# Lacrosse_Ball.net
KiCad netlist of a schematic drawn in Altium Designer
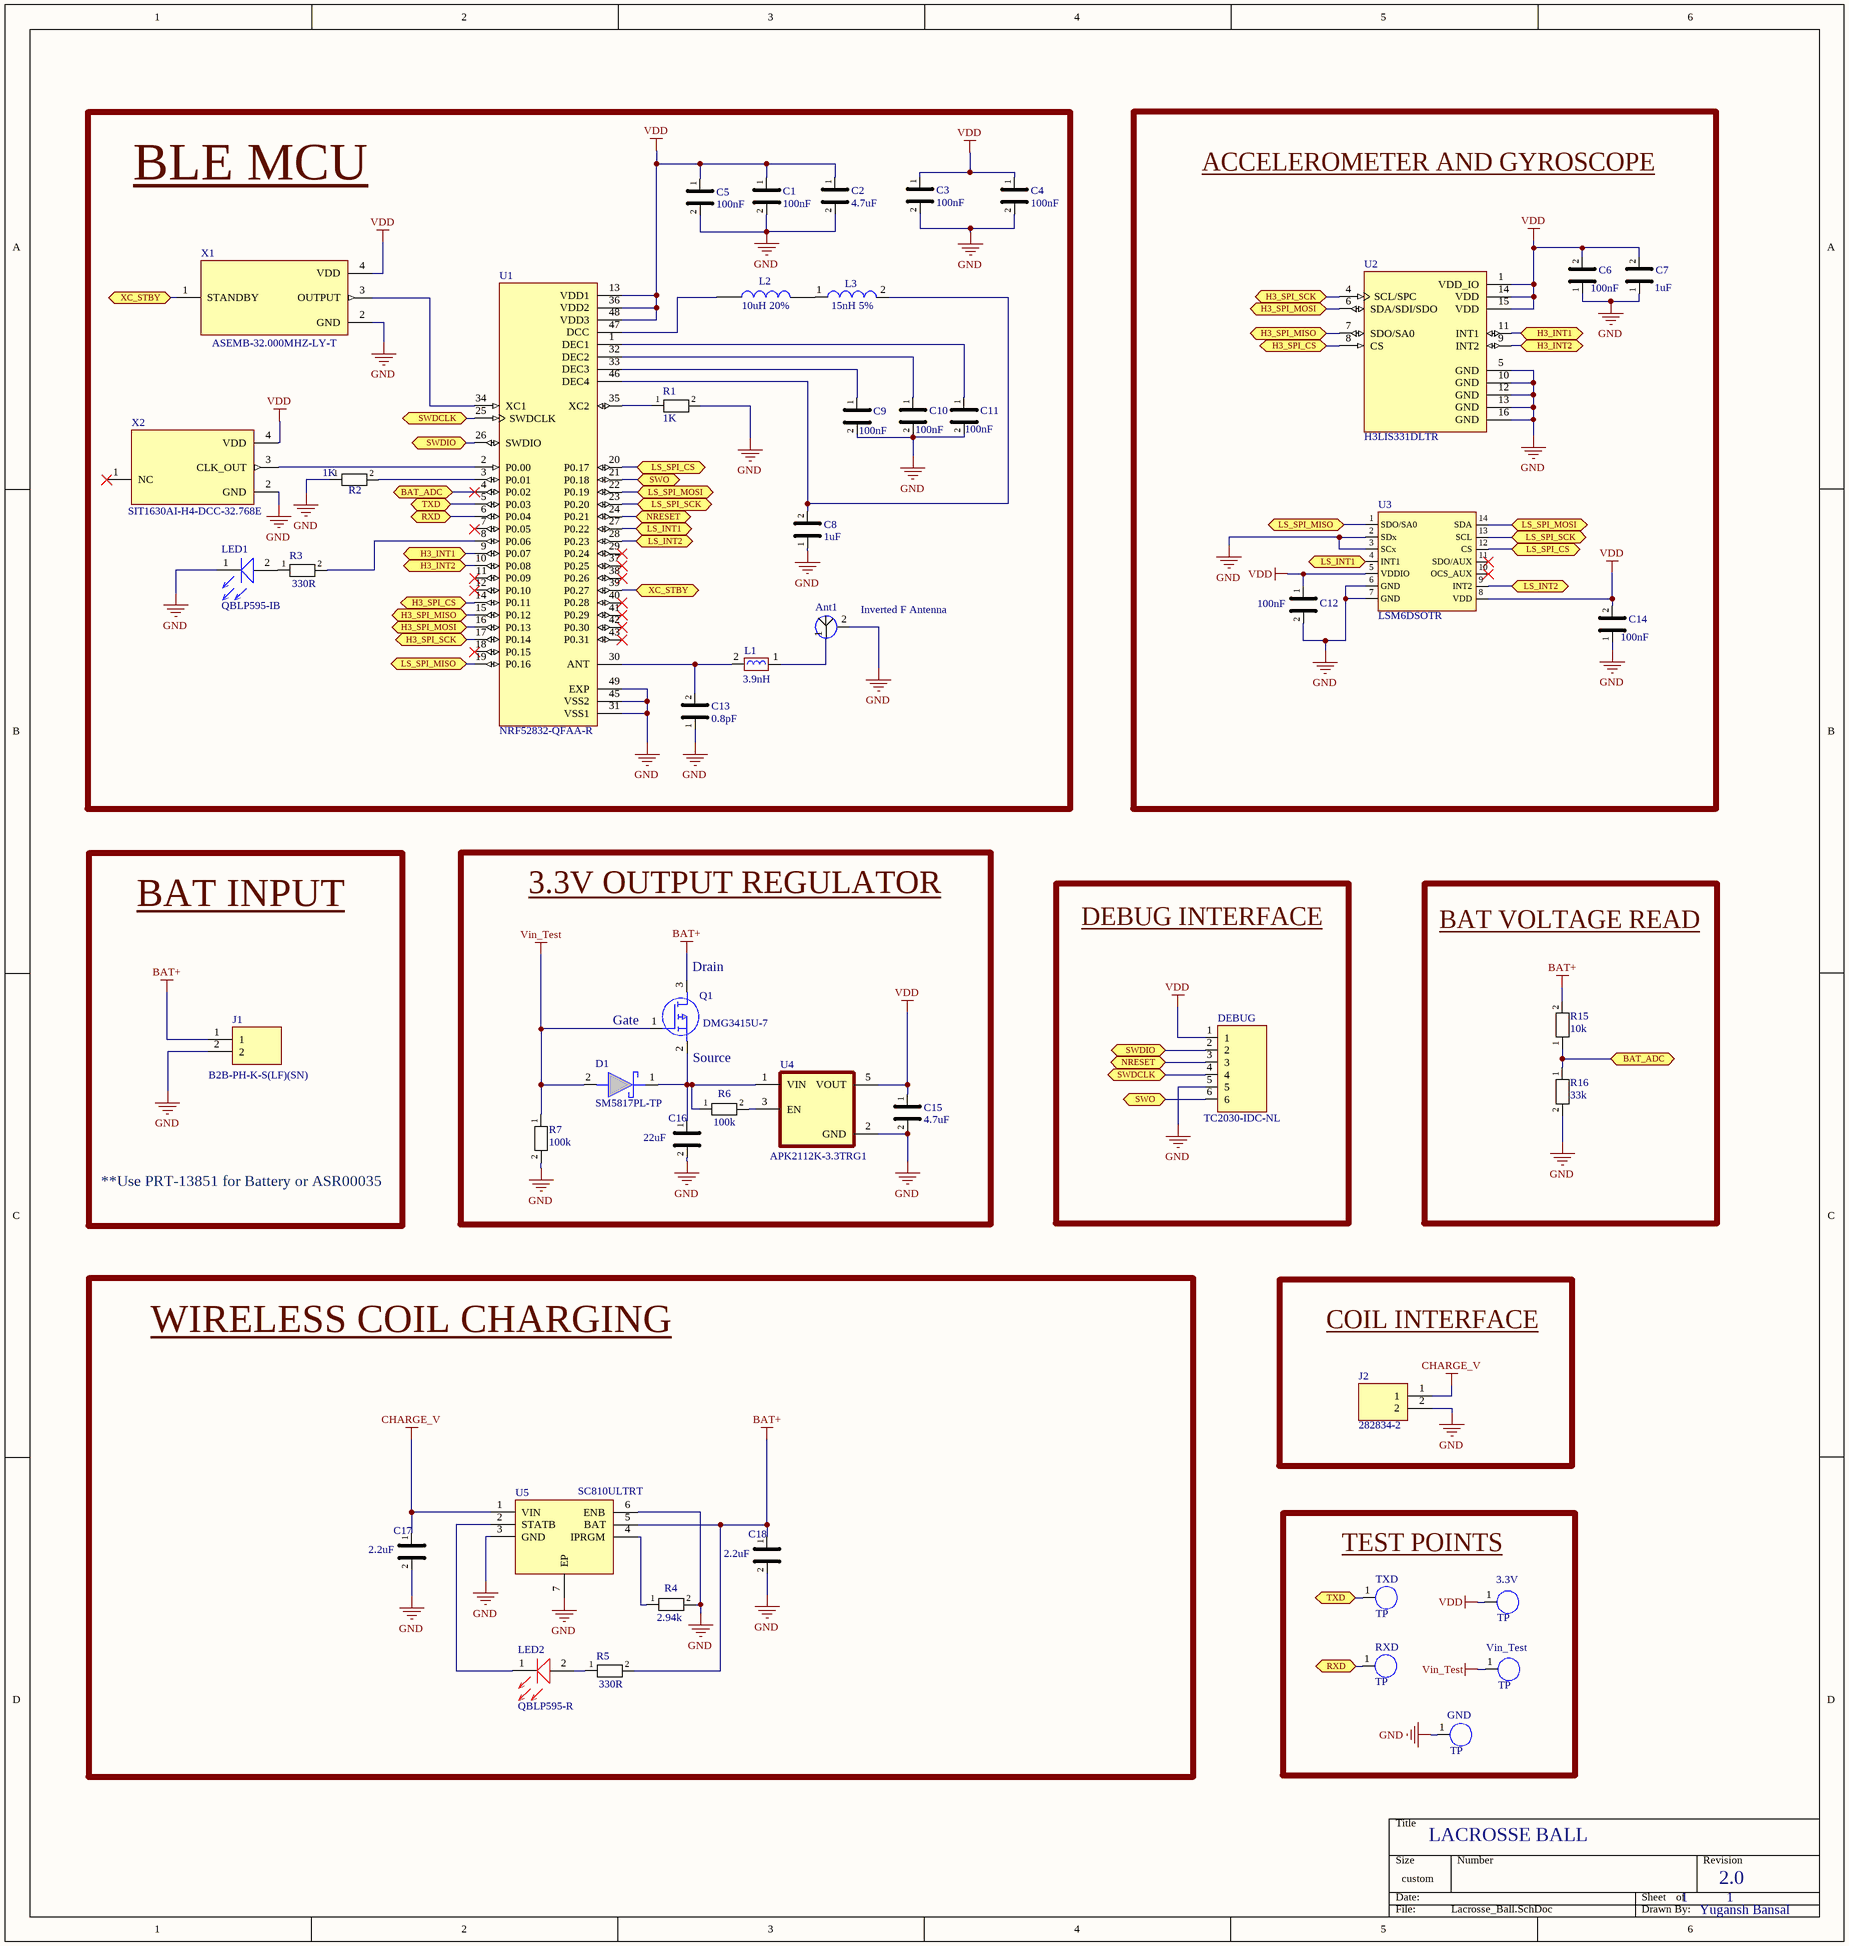
[diagram p0: Lacrosse_Ball.SchDoc]

(export (version "E")
  (design (tool "Eeschema 10.0.6"))
  (components
    (comp (ref "3.3V") (value "TP") (footprint "TP") (libsource (lib "NRF52832_Ball") (part "TP")))
    (comp (ref "Ant1")
      (value "Inverted F Antenna")
      (footprint "Inverted_F_Antenna")
      (libsource (lib "NRF52832_Ball") (part "Antenna"))
    )
    (comp (ref "C1")
      (value "100nF")
      (footprint "C0201")
      (fields
        (field (name "MF") "muRata(村田)")
        (field (name "MP") "GRM033Z71A104KE14D")
        (field (name "JLCPCBPART#") "C161494")
      )
      (libsource (lib "NRF52832_Ball") (part "Capacitor 100nF"))
    )
    (comp (ref "C2")
      (value "4.7uF")
      (footprint "C0402")
      (fields
        (field (name "MF") "SAMSUNG(三星)")
        (field (name "MP") "CL05A475MP5NRNC")
        (field (name "JLCPCBPART#") "C23733")
      )
      (libsource (lib "NRF52832_Ball") (part "capacitor 4.7uF"))
    )
    (comp (ref "C3")
      (value "100nF")
      (footprint "C0201")
      (fields
        (field (name "MF") "muRata(村田)")
        (field (name "MP") "GRM033Z71A104KE14D")
        (field (name "JLCPCBPART#") "C161494")
      )
      (libsource (lib "NRF52832_Ball") (part "Capacitor 100nF"))
    )
    (comp (ref "C4")
      (value "100nF")
      (footprint "C0201")
      (fields
        (field (name "MF") "muRata(村田)")
        (field (name "MP") "GRM033Z71A104KE14D")
        (field (name "JLCPCBPART#") "C161494")
      )
      (libsource (lib "NRF52832_Ball") (part "Capacitor 100nF"))
    )
    (comp (ref "C5")
      (value "100nF")
      (footprint "C0201")
      (fields
        (field (name "MF") "muRata(村田)")
        (field (name "MP") "GRM033Z71A104KE14D")
        (field (name "JLCPCBPART#") "C161494")
      )
      (libsource (lib "NRF52832_Ball") (part "Capacitor 100nF"))
    )
    (comp (ref "C6")
      (value "100nF")
      (footprint "C0201")
      (fields
        (field (name "MF") "muRata(村田)")
        (field (name "MP") "GRM033Z71A104KE14D")
        (field (name "JLCPCBPART#") "C161494")
      )
      (libsource (lib "NRF52832_Ball") (part "Capacitor 100nF"))
    )
    (comp (ref "C7")
      (value "1uF")
      (footprint "C0402")
      (fields
        (field (name "MF") "muRata(村田)")
        (field (name "MP") "GRM155Z71A105KE01D")
        (field (name "JLCPCBPART#") "C528974")
      )
      (libsource (lib "NRF52832_Ball") (part "Capacitor 1uF"))
    )
    (comp (ref "C8")
      (value "1uF")
      (footprint "C0402")
      (fields
        (field (name "MF") "muRata(村田)")
        (field (name "MP") "GRM155Z71A105KE01D")
        (field (name "JLCPCBPART#") "C528974")
      )
      (libsource (lib "NRF52832_Ball") (part "Capacitor 1uF"))
    )
    (comp (ref "C9")
      (value "100nF")
      (footprint "C0201")
      (fields
        (field (name "MF") "muRata(村田)")
        (field (name "MP") "GRM033Z71A104KE14D")
        (field (name "JLCPCBPART#") "C161494")
      )
      (libsource (lib "NRF52832_Ball") (part "Capacitor 100nF"))
    )
    (comp (ref "C10")
      (value "100nF")
      (footprint "C0201")
      (fields
        (field (name "MF") "muRata(村田)")
        (field (name "MP") "GRM033Z71A104KE14D")
        (field (name "JLCPCBPART#") "C161494")
      )
      (libsource (lib "NRF52832_Ball") (part "Capacitor 100nF"))
    )
    (comp (ref "C11")
      (value "100nF")
      (footprint "C0201")
      (fields
        (field (name "MF") "muRata(村田)")
        (field (name "MP") "GRM033Z71A104KE14D")
        (field (name "JLCPCBPART#") "C161494")
      )
      (libsource (lib "NRF52832_Ball") (part "Capacitor 100nF"))
    )
    (comp (ref "C12")
      (value "100nF")
      (footprint "C0201")
      (fields
        (field (name "MF") "muRata(村田)")
        (field (name "MP") "GRM033Z71A104KE14D")
        (field (name "JLCPCBPART#") "C161494")
      )
      (libsource (lib "NRF52832_Ball") (part "Capacitor 100nF"))
    )
    (comp (ref "C13")
      (value "0.8pF")
      (footprint "C0201")
      (fields
        (field (name "MF") "YAGEO(国巨)")
        (field (name "MP") "CC0201CRNPO9BNR80")
        (field (name "JLCPCBPART#") "C327151")
      )
      (libsource (lib "NRF52832_Ball") (part "Capacitor 0.8pF"))
    )
    (comp (ref "C14")
      (value "100nF")
      (footprint "C0201")
      (fields
        (field (name "MF") "muRata(村田)")
        (field (name "MP") "GRM033Z71A104KE14D")
        (field (name "JLCPCBPART#") "C161494")
      )
      (libsource (lib "NRF52832_Ball") (part "Capacitor 100nF"))
    )
    (comp (ref "C15")
      (value "4.7uF")
      (footprint "C0402")
      (fields
        (field (name "MF") "SAMSUNG(三星)")
        (field (name "MP") "CL05A475MP5NRNC")
        (field (name "JLCPCBPART#") "C23733")
      )
      (libsource (lib "NRF52832_Ball") (part "capacitor 4.7uF"))
    )
    (comp (ref "C16")
      (value "22uF")
      (footprint "C0603")
      (fields
        (field (name "MF") "muRata(村田)")
        (field (name "MP") "GRM188R61A226ME15D")
        (field (name "JLCPCBPART#") "C84419")
      )
      (libsource (lib "NRF52832_Ball") (part "capacitor 22uF"))
    )
    (comp (ref "C17")
      (value "2.2uF")
      (footprint "C0603")
      (fields
        (field (name "MF") "muRata(村田)")
        (field (name "MP") "GRM188R61A226ME15D")
        (field (name "JLCPCBPART#") "C84419")
      )
      (libsource (lib "NRF52832_Ball") (part "capacitor 22uF"))
    )
    (comp (ref "C18")
      (value "2.2uF")
      (footprint "C0603")
      (fields
        (field (name "MF") "muRata(村田)")
        (field (name "MP") "GRM188R61A226ME15D")
        (field (name "JLCPCBPART#") "C84419")
      )
      (libsource (lib "NRF52832_Ball") (part "capacitor 22uF"))
    )
    (comp (ref "D1")
      (value "SM5817PL-TP")
      (footprint "SM5817PL-TP")
      (description "DIODE SCHOTTKY 20V 1A SOD123FL")
      (libsource (lib "NRF52832_Ball") (part "SM5817PL-TP"))
    )
    (comp (ref "DEBUG")
      (value "TC2030-IDC-NL")
      (footprint "TC2030-IDC-NL")
      (description "Tag Connector 6POS")
      (libsource (lib "NRF52832_Ball") (part "TC2030-IDC-NL"))
    )
    (comp (ref "GND") (value "TP") (footprint "TP") (libsource (lib "NRF52832_Ball") (part "TP")))
    (comp (ref "J1")
      (value "B2B-PH-K-S(LF)(SN)")
      (footprint "B2B-PH-K-S(LF)(SN)")
      (description "CONN HEADER VERT 2POS 2MM")
      (libsource (lib "NRF52832_Ball") (part "B2B-PH-K-S(LF)(SN)"))
    )
    (comp (ref "J2")
      (value "282834-2")
      (footprint "282834-2")
      (description "TERM BLK 2P SIDE ENT 2.54MM PCB")
      (libsource (lib "NRF52832_Ball") (part "282834-2"))
    )
    (comp (ref "L1")
      (value "3.9nH")
      (footprint "C0201")
      (fields
        (field (name "MF") "TDK")
        (field (name "MP") "MLG0603S3N9ST000")
        (field (name "JLCPCBPART#") "C136219")
      )
      (libsource (lib "NRF52832_Ball") (part "3.9nH  Inductor"))
    )
    (comp (ref "L2")
      (value "10uH 20%")
      (footprint "LQM18DN100M70L")
      (description "FIXED IND 10UH 300MA")
      (libsource (lib "NRF52832_Ball") (part "LQM18DN100M70L"))
    )
    (comp (ref "L3")
      (value "15nH 5%")
      (footprint "LQG15HZ15NJ02D")
      (description "FIXED IND 15NH 450MA 320MOHM SMD")
      (libsource (lib "NRF52832_Ball") (part "LQG15HZ15NJ02D"))
    )
    (comp (ref "LED1")
      (value "QBLP595-IB")
      (footprint "QBLP595-IB")
      (description "LED BLUE CLEAR 0402 SMD")
      (libsource (lib "NRF52832_Ball") (part "QBLP595-IB"))
    )
    (comp (ref "LED2")
      (value "QBLP595-R")
      (footprint "QBLP595-R")
      (description "LED RED CLEAR 0402 SMD")
      (libsource (lib "NRF52832_Ball") (part "QBLP595-R"))
    )
    (comp (ref "Q1")
      (value "DMG3415U-7")
      (footprint "DMG3415U-7")
      (description "MOSFET P-CH 20V 4A SOT23-3")
      (libsource (lib "NRF52832_Ball") (part "DMG3415U-7"))
    )
    (comp (ref "R1")
      (value "1K")
      (footprint "R0201")
      (fields
        (field (name "MF") "YAGEO(国巨)")
        (field (name "MP") "RC0201JR-071KL")
        (field (name "JLCPCBPART#") "C131396")
      )
      (libsource (lib "NRF52832_Ball") (part "resistor 1K"))
    )
    (comp (ref "R2")
      (value "1K")
      (footprint "R0201")
      (fields
        (field (name "MF") "YAGEO(国巨)")
        (field (name "MP") "RC0201JR-071KL")
        (field (name "JLCPCBPART#") "C131396")
      )
      (libsource (lib "NRF52832_Ball") (part "resistor 1K"))
    )
    (comp (ref "R3")
      (value "330R")
      (footprint "R0201")
      (description "Resistor 0201 330ohm")
      (fields (field (name "MF") "YAGEO(国巨)") (field (name "MP") "RC0201JR-071KL"))
      (libsource (lib "NRF52832_Ball") (part "resistor 1K"))
    )
    (comp (ref "R4")
      (value "2.94k")
      (footprint "R0201")
      (description "Resistor 0201 2.94kohm")
      (fields (field (name "MF") "YAGEO(国巨)") (field (name "MP") "RC0201JR-071KL"))
      (libsource (lib "NRF52832_Ball") (part "resistor 1K"))
    )
    (comp (ref "R5")
      (value "330R")
      (footprint "R0201")
      (description "Resistor 0201 330ohm")
      (fields (field (name "MF") "YAGEO(国巨)") (field (name "MP") "RC0201JR-071KL"))
      (libsource (lib "NRF52832_Ball") (part "resistor 1K"))
    )
    (comp (ref "R6")
      (value "100k")
      (footprint "R0201")
      (description "RC0201FR-07100KL  RES 100K OHM 1% 1/20W 0201")
      (fields (field (name "MF") "Vishay Intertech") (field (name "MP") "CRCW02014K70JNED"))
      (libsource (lib "NRF52832_Ball") (part "4.7K"))
    )
    (comp (ref "R7")
      (value "100k")
      (footprint "R0201")
      (description "RC0201FR-07100KL  RES 100K OHM 1% 1/20W 0201")
      (fields (field (name "MF") "Vishay Intertech") (field (name "MP") "CRCW02014K70JNED"))
      (libsource (lib "NRF52832_Ball") (part "4.7K"))
    )
    (comp (ref "R15")
      (value "10k")
      (footprint "R0201")
      (description "10k 1% Chip resistor")
      (fields (field (name "MF") "Vishay Intertech") (field (name "MP") "CRCW02014K70JNED"))
      (libsource (lib "NRF52832_Ball") (part "4.7K"))
    )
    (comp (ref "R16")
      (value "33k")
      (footprint "R0201")
      (description "33k 1% chip resistor")
      (fields (field (name "MF") "Vishay Intertech") (field (name "MP") "CRCW02014K70JNED"))
      (libsource (lib "NRF52832_Ball") (part "4.7K"))
    )
    (comp (ref "RXD") (value "TP") (footprint "TP") (libsource (lib "NRF52832_Ball") (part "TP")))
    (comp (ref "TXD") (value "TP") (footprint "TP") (libsource (lib "NRF52832_Ball") (part "TP")))
    (comp (ref "U1")
      (value "NRF52832-QFAA-R")
      (footprint "VFQFN-48")
      (description "2Mbps 2.4GHz Bluetooth 2.4GHz I2C,SPI,UART QFN-48-EP(6x6) RF Transceiver ICs ROHS")
      (fields (field (name "MF") "Nordic Semicon") (field (name "JLCPCBPART#") "C77540"))
      (libsource (lib "NRF52832_Ball") (part "NRF52832-QFAA-R"))
    )
    (comp (ref "U2")
      (value "H3LIS331DLTR")
      (footprint "TFLGA-16(3x3)")
      (description "TFLGA-16(3x3) Attitude Sensor/Gyroscope ROHS")
      (fields (field (name "MF") "STMicroelectronics") (field (name "JLCPCBPART#") "C2655074"))
      (libsource (lib "NRF52832_Ball") (part "H3LIS331DLTR"))
    )
    (comp (ref "U3")
      (value "LSM6DSOTR")
      (footprint "LGA-14(2.5x3)")
      (description "LGA-14(2.5x3) Attitude Sensor/Gyroscope ROHS")
      (fields (field (name "MF") "STMicroelectronics") (field (name "JLCPCBPART#") "C2655100"))
      (libsource (lib "NRF52832_Ball") (part "LSM6DSOTR"))
    )
    (comp (ref "U4")
      (value "APK2112K-3.3TRG1")
      (footprint "SOT-25-5")
      (description "65dB@(100Hz,1kHz) 600mA Fixed 3.3V~3.3V Positive 6V SOT-23-5 Linear Voltage Regulators (LDO) ROHS")
      (fields (field (name "MF") "Diodes Incorporated") (field (name "MP") "AP2112K-3.3TRG1"))
      (libsource (lib "NRF52832_Ball") (part "APK2112K-3.3TRG1"))
    )
    (comp (ref "U5")
      (value "SC810ULTRT")
      (footprint "SC810ULTRT")
      (description "IC BATT CHG LI-ION 1CELL 6MLP")
      (libsource (lib "NRF52832_Ball") (part "SC810ULTRT"))
    )
    (comp (ref "Vin_Test") (value "TP") (footprint "TP") (libsource (lib "NRF52832_Ball") (part "TP")))
    (comp (ref "X1")
      (value "ASEMB-32.000MHZ-LY-T")
      (footprint "ASEMB-32.000MHZ-LY-T")
      (description "MEMS OSC XO 32.0000MHZ CMOS SMD")
      (libsource (lib "NRF52832_Ball") (part "ASEMB-32.000MHZ-LY-T"))
    )
    (comp (ref "X2")
      (value "SIT1630AI-H4-DCC-32.768E")
      (footprint "SIT1630AI-H4-DCC-32.768E")
      (description "MEMS OSC XO 32.7680KHZ LVCMOS")
      (libsource (lib "NRF52832_Ball") (part "SIT1630AI-H4-DCC-32.768E"))
    )
  )
  (nets
    (net (code "1") (name "/BAT_ADC") (class "Default")
      (node (ref "R15") (pin "1") (pintype "passive"))
      (node (ref "R16") (pin "1") (pintype "passive"))
      (node (ref "U1") (pin "4") (pinfunction "P0.02_4") (pintype "bidirectional"))
    )
    (net (code "2") (name "/H3_INT1") (class "Default")
      (node (ref "U1") (pin "9") (pinfunction "P0.07_9") (pintype "bidirectional"))
      (node (ref "U2") (pin "11") (pinfunction "INT1_11") (pintype "bidirectional"))
    )
    (net (code "3") (name "/H3_INT2") (class "Default")
      (node (ref "U1") (pin "10") (pinfunction "P0.08_10") (pintype "bidirectional"))
      (node (ref "U2") (pin "9") (pinfunction "INT2_9") (pintype "bidirectional"))
    )
    (net (code "4") (name "/H3_SPI_CS") (class "Default")
      (node (ref "U1") (pin "14") (pinfunction "P0.11_14") (pintype "bidirectional"))
      (node (ref "U2") (pin "8") (pinfunction "CS_8") (pintype "input"))
    )
    (net (code "5") (name "/H3_SPI_MISO") (class "Default")
      (node (ref "U1") (pin "15") (pinfunction "P0.12_15") (pintype "bidirectional"))
      (node (ref "U2") (pin "7") (pinfunction "SDO/SA0_7") (pintype "bidirectional"))
    )
    (net (code "6") (name "/H3_SPI_MOSI") (class "Default")
      (node (ref "U1") (pin "16") (pinfunction "P0.13_16") (pintype "bidirectional"))
      (node (ref "U2") (pin "6") (pinfunction "SDA/SDI/SDO_6") (pintype "bidirectional"))
    )
    (net (code "7") (name "/H3_SPI_SCK") (class "Default")
      (node (ref "U1") (pin "17") (pinfunction "P0.14_17") (pintype "bidirectional"))
      (node (ref "U2") (pin "4") (pinfunction "SCL/SPC_4") (pintype "input"))
    )
    (net (code "8") (name "/LS_INT1") (class "Default")
      (node (ref "U1") (pin "27") (pinfunction "P0.22_27") (pintype "bidirectional"))
      (node (ref "U3") (pin "4") (pinfunction "INT1_4") (pintype "passive"))
    )
    (net (code "9") (name "/LS_INT2") (class "Default")
      (node (ref "U1") (pin "28") (pinfunction "P0.23_28") (pintype "bidirectional"))
      (node (ref "U3") (pin "9") (pinfunction "INT2_9") (pintype "passive"))
    )
    (net (code "10") (name "/LS_SPI_CS") (class "Default")
      (node (ref "U1") (pin "20") (pinfunction "P0.17_20") (pintype "bidirectional"))
      (node (ref "U3") (pin "12") (pinfunction "CS_12") (pintype "passive"))
    )
    (net (code "11") (name "/LS_SPI_MISO") (class "Default")
      (node (ref "U1") (pin "19") (pinfunction "P0.16_19") (pintype "bidirectional"))
      (node (ref "U3") (pin "1") (pinfunction "SDO/SA0_1") (pintype "passive"))
    )
    (net (code "12") (name "/LS_SPI_MOSI") (class "Default")
      (node (ref "U1") (pin "22") (pinfunction "P0.19_22") (pintype "bidirectional"))
      (node (ref "U3") (pin "14") (pinfunction "SDA_14") (pintype "passive"))
    )
    (net (code "13") (name "/LS_SPI_SCK") (class "Default")
      (node (ref "U1") (pin "23") (pinfunction "P0.20_23") (pintype "bidirectional"))
      (node (ref "U3") (pin "13") (pinfunction "SCL_13") (pintype "passive"))
    )
    (net (code "14") (name "/NRESET") (class "Default")
      (node (ref "DEBUG") (pin "3") (pinfunction "3_3") (pintype "passive"))
      (node (ref "U1") (pin "24") (pinfunction "P0.21_24") (pintype "bidirectional"))
    )
    (net (code "15") (name "/RXD") (class "Default")
      (node (ref "RXD") (pin "1") (pintype "passive"))
      (node (ref "U1") (pin "6") (pinfunction "P0.04_6") (pintype "bidirectional"))
    )
    (net (code "16") (name "/SWDCLK") (class "Default")
      (node (ref "DEBUG") (pin "4") (pinfunction "4_4") (pintype "passive"))
      (node (ref "U1") (pin "25") (pinfunction "SWDCLK_25") (pintype "input"))
    )
    (net (code "17") (name "/SWDIO") (class "Default")
      (node (ref "DEBUG") (pin "2") (pinfunction "2_2") (pintype "passive"))
      (node (ref "U1") (pin "26") (pinfunction "SWDIO_26") (pintype "bidirectional"))
    )
    (net (code "18") (name "/SWO") (class "Default")
      (node (ref "DEBUG") (pin "6") (pinfunction "6_6") (pintype "passive"))
      (node (ref "U1") (pin "21") (pinfunction "P0.18_21") (pintype "bidirectional"))
    )
    (net (code "19") (name "/TXD") (class "Default")
      (node (ref "TXD") (pin "1") (pintype "passive"))
      (node (ref "U1") (pin "5") (pinfunction "P0.03_5") (pintype "bidirectional"))
    )
    (net (code "20") (name "/XC_STBY") (class "Default")
      (node (ref "U1") (pin "39") (pinfunction "P0.27_39") (pintype "bidirectional"))
      (node (ref "X1") (pin "1") (pinfunction "STANDBY_1") (pintype "passive"))
    )
    (net (code "21") (name "BAT+") (class "Default")
      (node (ref "C18") (pin "1") (pintype "passive"))
      (node (ref "J1") (pin "1") (pinfunction "1_1") (pintype "passive"))
      (node (ref "Q1") (pin "3") (pinfunction "D_3") (pintype "passive"))
      (node (ref "R15") (pin "2") (pintype "passive"))
      (node (ref "R5") (pin "2") (pintype "passive"))
      (node (ref "U5") (pin "5") (pinfunction "BAT_5") (pintype "passive"))
    )
    (net (code "22") (name "CHARGE_V") (class "Default")
      (node (ref "C17") (pin "1") (pintype "passive"))
      (node (ref "J2") (pin "1") (pinfunction "1_1") (pintype "passive"))
      (node (ref "U5") (pin "1") (pinfunction "VIN_1") (pintype "passive"))
    )
    (net (code "23") (name "GND") (class "Default")
      (node (ref "Ant1") (pin "2") (pintype "passive"))
      (node (ref "C1") (pin "2") (pintype "passive"))
      (node (ref "C10") (pin "2") (pintype "passive"))
      (node (ref "C11") (pin "2") (pintype "passive"))
      (node (ref "C12") (pin "2") (pintype "passive"))
      (node (ref "C13") (pin "1") (pintype "passive"))
      (node (ref "C14") (pin "1") (pintype "passive"))
      (node (ref "C15") (pin "2") (pintype "passive"))
      (node (ref "C16") (pin "2") (pintype "passive"))
      (node (ref "C17") (pin "2") (pintype "passive"))
      (node (ref "C18") (pin "2") (pintype "passive"))
      (node (ref "C2") (pin "2") (pintype "passive"))
      (node (ref "C3") (pin "2") (pintype "passive"))
      (node (ref "C4") (pin "2") (pintype "passive"))
      (node (ref "C5") (pin "2") (pintype "passive"))
      (node (ref "C6") (pin "1") (pintype "passive"))
      (node (ref "C7") (pin "1") (pintype "passive"))
      (node (ref "C8") (pin "1") (pintype "passive"))
      (node (ref "C9") (pin "2") (pintype "passive"))
      (node (ref "DEBUG") (pin "5") (pinfunction "5_5") (pintype "passive"))
      (node (ref "GND") (pin "1") (pintype "passive"))
      (node (ref "J1") (pin "2") (pinfunction "2_2") (pintype "passive"))
      (node (ref "J2") (pin "2") (pinfunction "2_2") (pintype "passive"))
      (node (ref "LED1") (pin "1") (pinfunction "CATHODE_(-)_1") (pintype "passive"))
      (node (ref "R1") (pin "2") (pintype "passive"))
      (node (ref "R16") (pin "2") (pintype "passive"))
      (node (ref "R2") (pin "1") (pintype "passive"))
      (node (ref "R4") (pin "2") (pintype "passive"))
      (node (ref "R7") (pin "2") (pintype "passive"))
      (node (ref "U1") (pin "31") (pinfunction "VSS1_31") (pintype "passive"))
      (node (ref "U1") (pin "45") (pinfunction "VSS2_45") (pintype "passive"))
      (node (ref "U1") (pin "49") (pinfunction "EXP_49") (pintype "passive"))
      (node (ref "U2") (pin "10") (pinfunction "GND_10") (pintype "passive"))
      (node (ref "U2") (pin "12") (pinfunction "GND_12") (pintype "passive"))
      (node (ref "U2") (pin "13") (pinfunction "GND_13") (pintype "passive"))
      (node (ref "U2") (pin "16") (pinfunction "GND_16") (pintype "passive"))
      (node (ref "U2") (pin "5") (pinfunction "GND_5") (pintype "passive"))
      (node (ref "U3") (pin "2") (pinfunction "SDx_2") (pintype "passive"))
      (node (ref "U3") (pin "3") (pinfunction "SCx_3") (pintype "passive"))
      (node (ref "U3") (pin "6") (pinfunction "GND_6") (pintype "passive"))
      (node (ref "U3") (pin "7") (pinfunction "GND_7") (pintype "passive"))
      (node (ref "U4") (pin "2") (pinfunction "GND_2") (pintype "passive"))
      (node (ref "U5") (pin "3") (pinfunction "GND_3") (pintype "passive"))
      (node (ref "U5") (pin "6") (pinfunction "ENB_6") (pintype "passive"))
      (node (ref "U5") (pin "7") (pinfunction "EP_7") (pintype "passive"))
      (node (ref "X1") (pin "2") (pinfunction "GND_2") (pintype "power_in"))
      (node (ref "X2") (pin "2") (pinfunction "GND_2") (pintype "power_in"))
    )
    (net (code "24") (name "Net-(Ant1-Pad1)") (class "Default")
      (node (ref "Ant1") (pin "1") (pintype "passive"))
      (node (ref "L1") (pin "1") (pintype "passive"))
    )
    (net (code "25") (name "Net-(D1-K)") (class "Default")
      (node (ref "C16") (pin "1") (pintype "passive"))
      (node (ref "D1") (pin "1") (pinfunction "K_1") (pintype "passive"))
      (node (ref "Q1") (pin "2") (pinfunction "S_2") (pintype "passive"))
      (node (ref "R6") (pin "1") (pintype "passive"))
      (node (ref "U4") (pin "1") (pinfunction "VIN_1") (pintype "power_in"))
    )
    (net (code "26") (name "Net-(L2-Pad2)") (class "Default")
      (node (ref "L2") (pin "2") (pinfunction "2_2") (pintype "passive"))
      (node (ref "L3") (pin "1") (pinfunction "1_1") (pintype "passive"))
    )
    (net (code "27") (name "Net-(LED1-ANODE_(+))") (class "Default")
      (node (ref "LED1") (pin "2") (pinfunction "ANODE_(+)_2") (pintype "passive"))
      (node (ref "R3") (pin "1") (pintype "passive"))
    )
    (net (code "28") (name "Net-(LED2-ANODE_(+))") (class "Default")
      (node (ref "LED2") (pin "2") (pinfunction "ANODE_(+)_2") (pintype "passive"))
      (node (ref "R5") (pin "1") (pintype "passive"))
    )
    (net (code "29") (name "Net-(LED2-CATHODE_(-))") (class "Default")
      (node (ref "LED2") (pin "1") (pinfunction "CATHODE_(-)_1") (pintype "passive"))
      (node (ref "U5") (pin "2") (pinfunction "STATB_2") (pintype "passive"))
    )
    (net (code "30") (name "Net-(U1-ANT)") (class "Default")
      (node (ref "C13") (pin "2") (pintype "passive"))
      (node (ref "L1") (pin "2") (pintype "passive"))
      (node (ref "U1") (pin "30") (pinfunction "ANT_30") (pintype "passive"))
    )
    (net (code "31") (name "Net-(U1-DCC)") (class "Default")
      (node (ref "L2") (pin "1") (pinfunction "1_1") (pintype "passive"))
      (node (ref "U1") (pin "47") (pinfunction "DCC_47") (pintype "passive"))
    )
    (net (code "32") (name "Net-(U1-DEC1)") (class "Default")
      (node (ref "C11") (pin "1") (pintype "passive"))
      (node (ref "U1") (pin "1") (pinfunction "DEC1_1") (pintype "passive"))
    )
    (net (code "33") (name "Net-(U1-DEC2)") (class "Default")
      (node (ref "C10") (pin "1") (pintype "passive"))
      (node (ref "U1") (pin "32") (pinfunction "DEC2_32") (pintype "passive"))
    )
    (net (code "34") (name "Net-(U1-DEC3)") (class "Default")
      (node (ref "C9") (pin "1") (pintype "passive"))
      (node (ref "U1") (pin "33") (pinfunction "DEC3_33") (pintype "passive"))
    )
    (net (code "35") (name "Net-(U1-DEC4)") (class "Default")
      (node (ref "C8") (pin "2") (pintype "passive"))
      (node (ref "L3") (pin "2") (pinfunction "2_2") (pintype "passive"))
      (node (ref "U1") (pin "46") (pinfunction "DEC4_46") (pintype "passive"))
    )
    (net (code "36") (name "Net-(U1-P0.00)") (class "Default")
      (node (ref "U1") (pin "2") (pinfunction "P0.00_2") (pintype "input"))
      (node (ref "X2") (pin "3") (pinfunction "CLK_OUT_3") (pintype "output"))
    )
    (net (code "37") (name "Net-(U1-P0.01)") (class "Default")
      (node (ref "R2") (pin "2") (pintype "passive"))
      (node (ref "U1") (pin "3") (pinfunction "P0.01_3") (pintype "bidirectional"))
    )
    (net (code "38") (name "Net-(U1-P0.06)") (class "Default")
      (node (ref "R3") (pin "2") (pintype "passive"))
      (node (ref "U1") (pin "8") (pinfunction "P0.06_8") (pintype "bidirectional"))
    )
    (net (code "39") (name "Net-(U1-XC1)") (class "Default")
      (node (ref "U1") (pin "34") (pinfunction "XC1_34") (pintype "input"))
      (node (ref "X1") (pin "3") (pinfunction "OUTPUT_3") (pintype "output"))
    )
    (net (code "40") (name "Net-(U1-XC2)") (class "Default")
      (node (ref "R1") (pin "1") (pintype "passive"))
      (node (ref "U1") (pin "35") (pinfunction "XC2_35") (pintype "bidirectional"))
    )
    (net (code "41") (name "Net-(U4-EN)") (class "Default")
      (node (ref "R6") (pin "2") (pintype "passive"))
      (node (ref "U4") (pin "3") (pinfunction "EN_3") (pintype "passive"))
    )
    (net (code "42") (name "Net-(U5-IPRGM)") (class "Default")
      (node (ref "R4") (pin "1") (pintype "passive"))
      (node (ref "U5") (pin "4") (pinfunction "IPRGM_4") (pintype "passive"))
    )
    (net (code "43") (name "VDD") (class "Default")
      (node (ref "3.3V") (pin "1") (pintype "passive"))
      (node (ref "C1") (pin "1") (pintype "passive"))
      (node (ref "C12") (pin "1") (pintype "passive"))
      (node (ref "C14") (pin "2") (pintype "passive"))
      (node (ref "C15") (pin "1") (pintype "passive"))
      (node (ref "C2") (pin "1") (pintype "passive"))
      (node (ref "C3") (pin "1") (pintype "passive"))
      (node (ref "C4") (pin "1") (pintype "passive"))
      (node (ref "C5") (pin "1") (pintype "passive"))
      (node (ref "C6") (pin "2") (pintype "passive"))
      (node (ref "C7") (pin "2") (pintype "passive"))
      (node (ref "DEBUG") (pin "1") (pinfunction "1_1") (pintype "passive"))
      (node (ref "U1") (pin "13") (pinfunction "VDD1_13") (pintype "passive"))
      (node (ref "U1") (pin "36") (pinfunction "VDD2_36") (pintype "passive"))
      (node (ref "U1") (pin "48") (pinfunction "VDD3_48") (pintype "passive"))
      (node (ref "U2") (pin "1") (pinfunction "VDD_IO_1") (pintype "power_in"))
      (node (ref "U2") (pin "14") (pinfunction "VDD_14") (pintype "power_in"))
      (node (ref "U2") (pin "15") (pinfunction "VDD_15") (pintype "power_in"))
      (node (ref "U3") (pin "5") (pinfunction "VDDIO_5") (pintype "passive"))
      (node (ref "U3") (pin "8") (pinfunction "VDD_8") (pintype "passive"))
      (node (ref "U4") (pin "5") (pinfunction "VOUT_5") (pintype "power_in"))
      (node (ref "X1") (pin "4") (pinfunction "VDD_4") (pintype "power_in"))
      (node (ref "X2") (pin "4") (pinfunction "VDD_4") (pintype "power_in"))
    )
    (net (code "44") (name "Vin_Test") (class "Default")
      (node (ref "D1") (pin "2") (pinfunction "A_2") (pintype "passive"))
      (node (ref "Q1") (pin "1") (pinfunction "G_1") (pintype "passive"))
      (node (ref "R7") (pin "1") (pintype "passive"))
      (node (ref "Vin_Test") (pin "1") (pintype "passive"))
    )
    (net (code "45") (name "unconnected-(U1-P0.05-Pad7)") (class "Default")
      (node (ref "U1") (pin "7") (pinfunction "P0.05_7") (pintype "bidirectional+no_connect"))
    )
    (net (code "46") (name "unconnected-(U1-P0.09-Pad11)") (class "Default")
      (node (ref "U1") (pin "11") (pinfunction "P0.09_11") (pintype "bidirectional+no_connect"))
    )
    (net (code "47") (name "unconnected-(U1-P0.10-Pad12)") (class "Default")
      (node (ref "U1") (pin "12") (pinfunction "P0.10_12") (pintype "bidirectional+no_connect"))
    )
    (net (code "48") (name "unconnected-(U1-P0.15-Pad18)") (class "Default")
      (node (ref "U1") (pin "18") (pinfunction "P0.15_18") (pintype "bidirectional+no_connect"))
    )
    (net (code "49") (name "unconnected-(U1-P0.24-Pad29)") (class "Default")
      (node (ref "U1") (pin "29") (pinfunction "P0.24_29") (pintype "bidirectional+no_connect"))
    )
    (net (code "50") (name "unconnected-(U1-P0.25-Pad37)") (class "Default")
      (node (ref "U1") (pin "37") (pinfunction "P0.25_37") (pintype "bidirectional+no_connect"))
    )
    (net (code "51") (name "unconnected-(U1-P0.26-Pad38)") (class "Default")
      (node (ref "U1") (pin "38") (pinfunction "P0.26_38") (pintype "bidirectional+no_connect"))
    )
    (net (code "52") (name "unconnected-(U1-P0.28-Pad40)") (class "Default")
      (node (ref "U1") (pin "40") (pinfunction "P0.28_40") (pintype "bidirectional+no_connect"))
    )
    (net (code "53") (name "unconnected-(U1-P0.29-Pad41)") (class "Default")
      (node (ref "U1") (pin "41") (pinfunction "P0.29_41") (pintype "bidirectional+no_connect"))
    )
    (net (code "54") (name "unconnected-(U1-P0.30-Pad42)") (class "Default")
      (node (ref "U1") (pin "42") (pinfunction "P0.30_42") (pintype "bidirectional+no_connect"))
    )
    (net (code "55") (name "unconnected-(U1-P0.31-Pad43)") (class "Default")
      (node (ref "U1") (pin "43") (pinfunction "P0.31_43") (pintype "bidirectional+no_connect"))
    )
    (net (code "56") (name "unconnected-(U3-OCS_AUX-Pad10)") (class "Default")
      (node (ref "U3") (pin "10") (pinfunction "OCS_AUX_10") (pintype "passive+no_connect"))
    )
    (net (code "57") (name "unconnected-(U3-SDO{slash}AUX-Pad11)") (class "Default")
      (node (ref "U3") (pin "11") (pinfunction "SDO/AUX_11") (pintype "passive+no_connect"))
    )
    (net (code "58") (name "unconnected-(X2-NC-Pad1)") (class "Default")
      (node (ref "X2") (pin "1") (pinfunction "NC_1") (pintype "passive+no_connect"))
    )
  )
)
